# 01_main.net
KiCad netlist of a schematic drawn in EAGLE
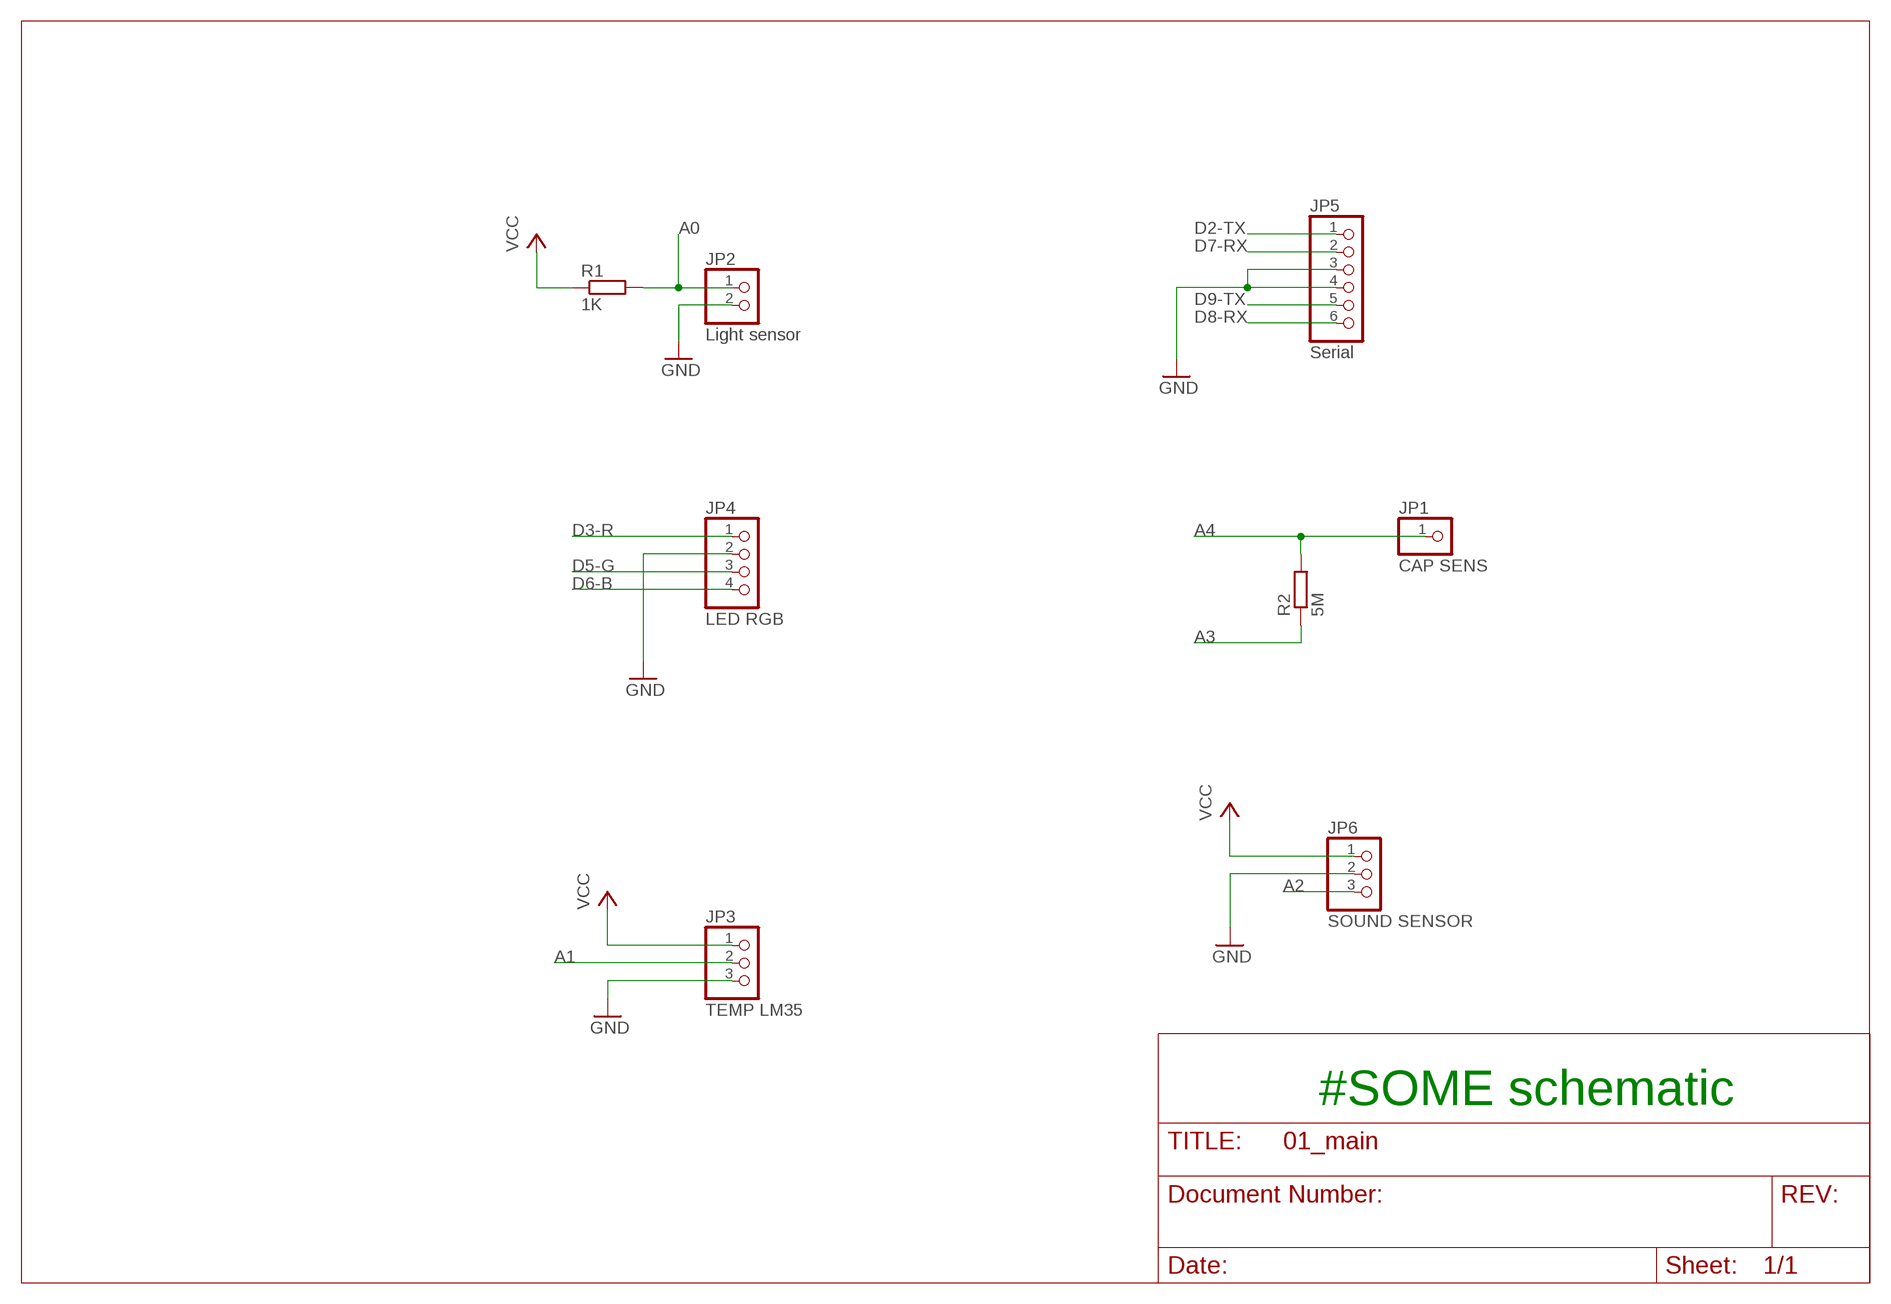
[diagram p0: schematic, sheet 1]

(export (version "E")
  (design (tool "Eeschema 10.0.6"))
  (components
    (comp (ref "JP1")
      (value "CAP SENS")
      (footprint "eagle-import:1X01")
      (libsource (lib "eagle-import") (part "PINHD-1X1"))
    )
    (comp (ref "JP2")
      (value "Light sensor")
      (footprint "eagle-import:1X02")
      (libsource (lib "eagle-import") (part "PINHD-1X2"))
    )
    (comp (ref "JP3")
      (value "TEMP LM35")
      (footprint "eagle-import:1X03")
      (libsource (lib "eagle-import") (part "PINHD-1X3"))
    )
    (comp (ref "JP4")
      (value "LED RGB")
      (footprint "eagle-import:1X04")
      (libsource (lib "eagle-import") (part "PINHD-1X4"))
    )
    (comp (ref "JP5")
      (value "Serial")
      (footprint "eagle-import:1X06")
      (libsource (lib "eagle-import") (part "PINHD-1X6"))
    )
    (comp (ref "JP6")
      (value "SOUND SENSOR")
      (footprint "eagle-import:1X03")
      (libsource (lib "eagle-import") (part "PINHD-1X3"))
    )
    (comp (ref "R1")
      (value "1K")
      (footprint "eagle-import:0204_5")
      (libsource (lib "eagle-import") (part "R-EU_0204/5"))
    )
    (comp (ref "R2")
      (value "5M")
      (footprint "eagle-import:0204_5")
      (libsource (lib "eagle-import") (part "R-EU_0204/5"))
    )
  )
  (nets
    (net (code "1") (name "/A0") (class "Default")
      (node (ref "JP2") (pin "1") (pinfunction "1_1") (pintype "passive"))
      (node (ref "R1") (pin "2") (pinfunction "2_2") (pintype "passive"))
    )
    (net (code "2") (name "/A1") (class "Default")
      (node (ref "JP3") (pin "2") (pinfunction "2_2") (pintype "passive"))
    )
    (net (code "3") (name "/A2") (class "Default")
      (node (ref "JP6") (pin "3") (pinfunction "3_3") (pintype "passive"))
    )
    (net (code "4") (name "/A3") (class "Default")
      (node (ref "R2") (pin "1") (pinfunction "1_1") (pintype "passive"))
    )
    (net (code "5") (name "/A4") (class "Default")
      (node (ref "JP1") (pin "1") (pinfunction "1_1") (pintype "passive"))
      (node (ref "R2") (pin "2") (pinfunction "2_2") (pintype "passive"))
    )
    (net (code "6") (name "/D2-TX") (class "Default")
      (node (ref "JP5") (pin "1") (pinfunction "1_1") (pintype "passive"))
    )
    (net (code "7") (name "/D3-R") (class "Default")
      (node (ref "JP4") (pin "1") (pinfunction "1_1") (pintype "passive"))
    )
    (net (code "8") (name "/D5-G") (class "Default")
      (node (ref "JP4") (pin "3") (pinfunction "3_3") (pintype "passive"))
    )
    (net (code "9") (name "/D6-B") (class "Default")
      (node (ref "JP4") (pin "4") (pinfunction "4_4") (pintype "passive"))
    )
    (net (code "10") (name "/D7-RX") (class "Default")
      (node (ref "JP5") (pin "2") (pinfunction "2_2") (pintype "passive"))
    )
    (net (code "11") (name "/D8-RX") (class "Default")
      (node (ref "JP5") (pin "6") (pinfunction "6_6") (pintype "passive"))
    )
    (net (code "12") (name "/D9-TX") (class "Default")
      (node (ref "JP5") (pin "5") (pinfunction "5_5") (pintype "passive"))
    )
    (net (code "13") (name "GND") (class "Default")
      (node (ref "JP2") (pin "2") (pinfunction "2_2") (pintype "passive"))
      (node (ref "JP3") (pin "3") (pinfunction "3_3") (pintype "passive"))
      (node (ref "JP4") (pin "2") (pinfunction "2_2") (pintype "passive"))
      (node (ref "JP5") (pin "3") (pinfunction "3_3") (pintype "passive"))
      (node (ref "JP5") (pin "4") (pinfunction "4_4") (pintype "passive"))
      (node (ref "JP6") (pin "2") (pinfunction "2_2") (pintype "passive"))
    )
    (net (code "14") (name "VCC") (class "Default")
      (node (ref "JP3") (pin "1") (pinfunction "1_1") (pintype "passive"))
      (node (ref "JP6") (pin "1") (pinfunction "1_1") (pintype "passive"))
      (node (ref "R1") (pin "1") (pinfunction "1_1") (pintype "passive"))
    )
  )
)
